# LedBlink.net
KiCad netlist of a schematic drawn in Altium Designer
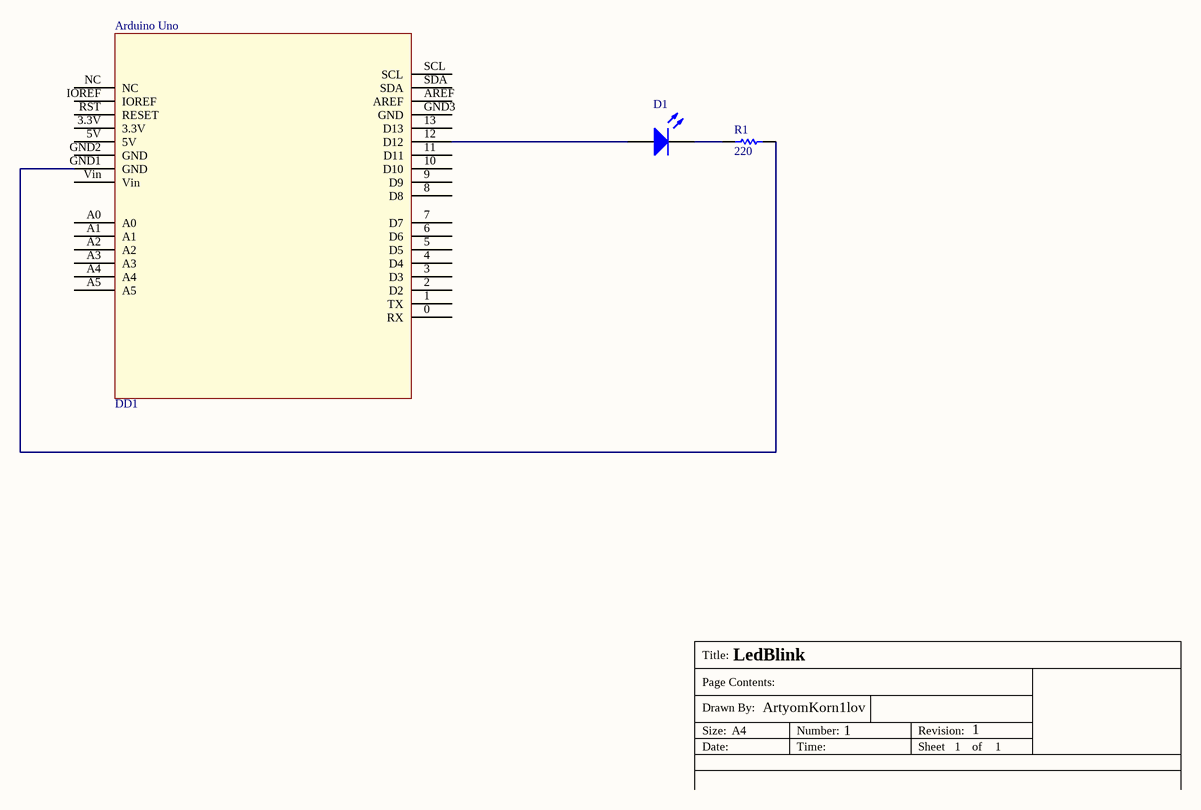
[diagram p0: LedBlink.SchDoc]

(export (version "E")
  (design (tool "Eeschema 10.0.6"))
  (components
    (comp (ref "Arduino Uno")
      (value "DD1")
      (footprint "ARDUINO UNO")
      (libsource (lib "Arduino") (part "ARDUINO UNO"))
    )
    (comp (ref "D1")
      (value "Light-Emitting Diode")
      (libsource (lib "Simulation Generic Components") (part "LED"))
    )
    (comp (ref "R1")
      (value "220")
      (description "Resistor")
      (libsource (lib "Simulation Generic Components") (part "Resistor"))
    )
  )
  (nets
    (net (code "1") (name "Net-(Arduino Uno-D12)") (class "Default")
      (node (ref "Arduino Uno") (pin "12") (pinfunction "D12_12") (pintype "passive"))
      (node (ref "D1") (pin "1") (pinfunction "A_1") (pintype "passive"))
    )
    (net (code "2") (name "Net-(Arduino Uno-GND-PadGND1)") (class "Default")
      (node (ref "Arduino Uno") (pin "GND1") (pinfunction "GND_GND1") (pintype "passive"))
      (node (ref "R1") (pin "2") (pinfunction "2_2") (pintype "passive"))
    )
    (net (code "3") (name "Net-(D1-K)") (class "Default")
      (node (ref "D1") (pin "2") (pinfunction "K_2") (pintype "passive"))
      (node (ref "R1") (pin "1") (pinfunction "1_1") (pintype "passive"))
    )
    (net (code "4") (name "unconnected-(Arduino Uno-D2-Pad2)") (class "Default")
      (node (ref "Arduino Uno") (pin "2") (pinfunction "D2_2") (pintype "passive"))
    )
    (net (code "5") (name "unconnected-(Arduino Uno-D3-Pad3)") (class "Default")
      (node (ref "Arduino Uno") (pin "3") (pinfunction "D3_3") (pintype "passive"))
    )
    (net (code "6") (name "unconnected-(Arduino Uno-D4-Pad4)") (class "Default")
      (node (ref "Arduino Uno") (pin "4") (pinfunction "D4_4") (pintype "passive"))
    )
    (net (code "7") (name "unconnected-(Arduino Uno-D5-Pad5)") (class "Default")
      (node (ref "Arduino Uno") (pin "5") (pinfunction "D5_5") (pintype "passive"))
    )
    (net (code "8") (name "unconnected-(Arduino Uno-D6-Pad6)") (class "Default")
      (node (ref "Arduino Uno") (pin "6") (pinfunction "D6_6") (pintype "passive"))
    )
    (net (code "9") (name "unconnected-(Arduino Uno-D7-Pad7)") (class "Default")
      (node (ref "Arduino Uno") (pin "7") (pinfunction "D7_7") (pintype "passive"))
    )
    (net (code "10") (name "unconnected-(Arduino Uno-D8-Pad8)") (class "Default")
      (node (ref "Arduino Uno") (pin "8") (pinfunction "D8_8") (pintype "passive"))
    )
    (net (code "11") (name "unconnected-(Arduino Uno-D9-Pad9)") (class "Default")
      (node (ref "Arduino Uno") (pin "9") (pinfunction "D9_9") (pintype "passive"))
    )
    (net (code "12") (name "unconnected-(Arduino Uno-D10-Pad10)") (class "Default")
      (node (ref "Arduino Uno") (pin "10") (pinfunction "D10_10") (pintype "passive"))
    )
    (net (code "13") (name "unconnected-(Arduino Uno-D11-Pad11)") (class "Default")
      (node (ref "Arduino Uno") (pin "11") (pinfunction "D11_11") (pintype "passive"))
    )
    (net (code "14") (name "unconnected-(Arduino Uno-D13-Pad13)") (class "Default")
      (node (ref "Arduino Uno") (pin "13") (pinfunction "D13_13") (pintype "passive"))
    )
    (net (code "15") (name "unconnected-(Arduino Uno-GND-PadGND2)") (class "Default")
      (node (ref "Arduino Uno") (pin "GND2") (pinfunction "GND_GND2") (pintype "passive"))
    )
    (net (code "16") (name "unconnected-(Arduino Uno-GND-PadGND3)") (class "Default")
      (node (ref "Arduino Uno") (pin "GND3") (pinfunction "GND_GND3") (pintype "passive"))
    )
    (net (code "17") (name "unconnected-(Arduino Uno-Pad3.3V)") (class "Default")
      (node (ref "Arduino Uno") (pin "3.3V") (pinfunction "3.3V_3.3V") (pintype "passive"))
    )
    (net (code "18") (name "unconnected-(Arduino Uno-Pad5V)") (class "Default")
      (node (ref "Arduino Uno") (pin "5V") (pinfunction "5V_5V") (pintype "passive"))
    )
    (net (code "19") (name "unconnected-(Arduino Uno-PadA0)") (class "Default")
      (node (ref "Arduino Uno") (pin "A0") (pinfunction "A0_A0") (pintype "passive"))
    )
    (net (code "20") (name "unconnected-(Arduino Uno-PadA1)") (class "Default")
      (node (ref "Arduino Uno") (pin "A1") (pinfunction "A1_A1") (pintype "passive"))
    )
    (net (code "21") (name "unconnected-(Arduino Uno-PadA2)") (class "Default")
      (node (ref "Arduino Uno") (pin "A2") (pinfunction "A2_A2") (pintype "passive"))
    )
    (net (code "22") (name "unconnected-(Arduino Uno-PadA3)") (class "Default")
      (node (ref "Arduino Uno") (pin "A3") (pinfunction "A3_A3") (pintype "passive"))
    )
    (net (code "23") (name "unconnected-(Arduino Uno-PadA4)") (class "Default")
      (node (ref "Arduino Uno") (pin "A4") (pinfunction "A4_A4") (pintype "passive"))
    )
    (net (code "24") (name "unconnected-(Arduino Uno-PadA5)") (class "Default")
      (node (ref "Arduino Uno") (pin "A5") (pinfunction "A5_A5") (pintype "passive"))
    )
    (net (code "25") (name "unconnected-(Arduino Uno-PadAREF)") (class "Default")
      (node (ref "Arduino Uno") (pin "AREF") (pinfunction "AREF_AREF") (pintype "passive"))
    )
    (net (code "26") (name "unconnected-(Arduino Uno-PadIOREF)") (class "Default")
      (node (ref "Arduino Uno") (pin "IOREF") (pinfunction "IOREF_IOREF") (pintype "passive"))
    )
    (net (code "27") (name "unconnected-(Arduino Uno-PadNC)") (class "Default")
      (node (ref "Arduino Uno") (pin "NC") (pinfunction "NC_NC") (pintype "passive"))
    )
    (net (code "28") (name "unconnected-(Arduino Uno-PadSCL)") (class "Default")
      (node (ref "Arduino Uno") (pin "SCL") (pinfunction "SCL_SCL") (pintype "passive"))
    )
    (net (code "29") (name "unconnected-(Arduino Uno-PadSDA)") (class "Default")
      (node (ref "Arduino Uno") (pin "SDA") (pinfunction "SDA_SDA") (pintype "passive"))
    )
    (net (code "30") (name "unconnected-(Arduino Uno-PadVin)") (class "Default")
      (node (ref "Arduino Uno") (pin "Vin") (pinfunction "Vin_Vin") (pintype "passive"))
    )
    (net (code "31") (name "unconnected-(Arduino Uno-RESET-PadRST)") (class "Default")
      (node (ref "Arduino Uno") (pin "RST") (pinfunction "RESET_RST") (pintype "passive"))
    )
    (net (code "32") (name "unconnected-(Arduino Uno-RX-Pad0)") (class "Default")
      (node (ref "Arduino Uno") (pin "0") (pinfunction "RX_0") (pintype "passive"))
    )
    (net (code "33") (name "unconnected-(Arduino Uno-TX-Pad1)") (class "Default")
      (node (ref "Arduino Uno") (pin "1") (pinfunction "TX_1") (pintype "passive"))
    )
  )
)
